# ALLPRINT-CAPBOARD-677512-ISO-PGM.net
KiCad netlist of a schematic drawn in Altium Designer
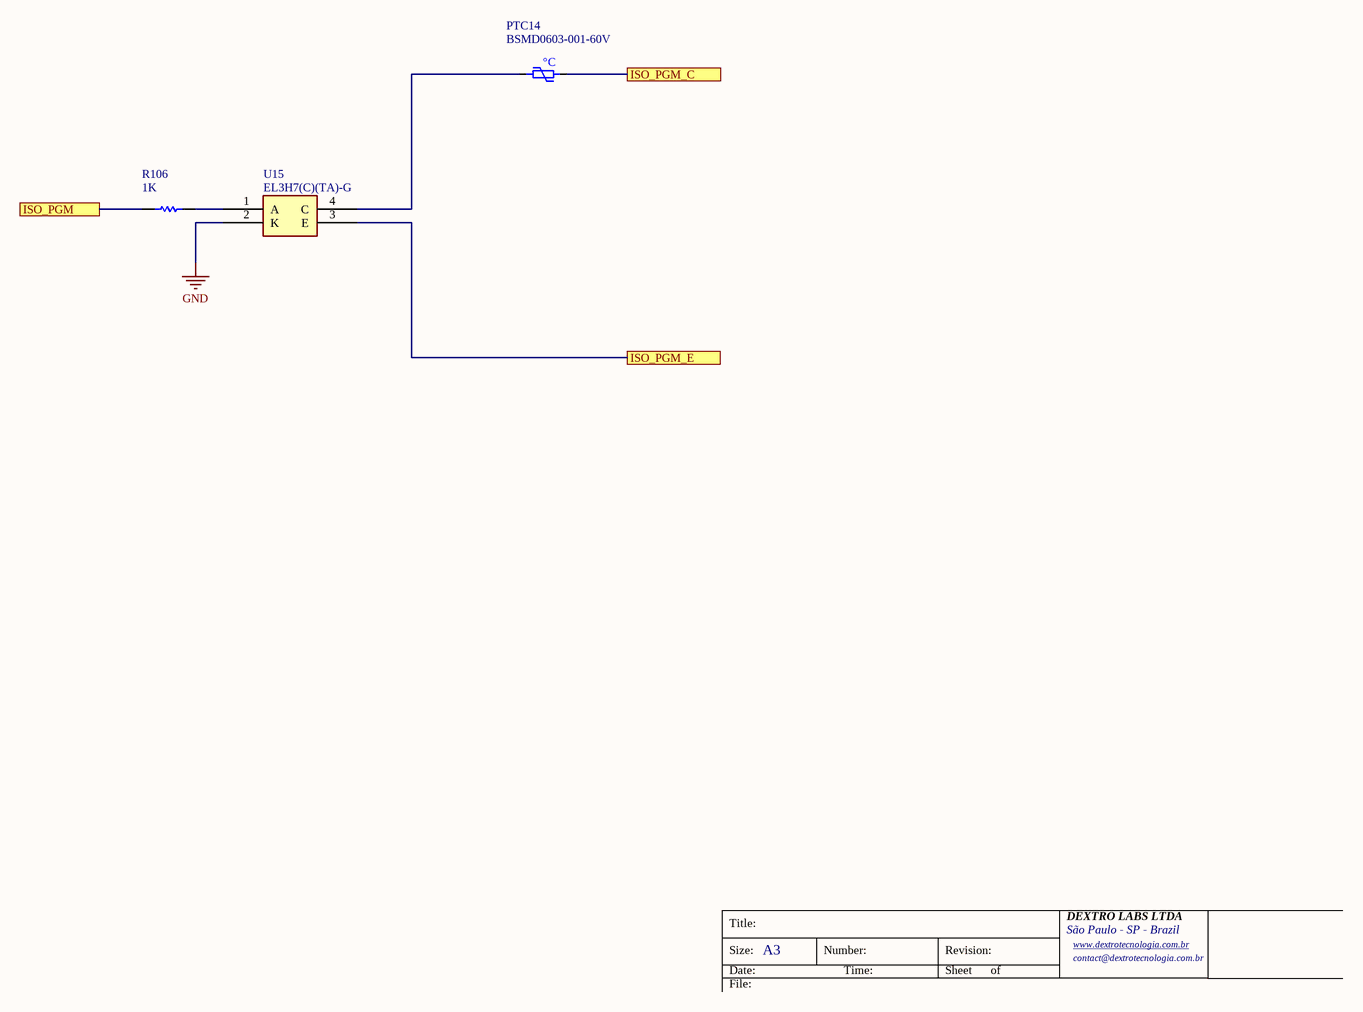
[diagram p0: ALLPRINT-CAPBOARD-677512-ISO-PGM.SchDoc]

(export (version "E")
  (design (tool "Eeschema 10.0.6"))
  (components
    (comp (ref "PTC14")
      (value "BSMD0603-001-60V")
      (footprint "PTC-0603")
      (description "60V 10mA 20A 50mA 15Ω 0603 PTC Resettable Fuses ROHS")
      (libsource (lib "dextro-labs") (part "PTC-FUSE-60V-10mA-0603"))
    )
    (comp (ref "R106")
      (value "1K")
      (footprint "RES-0603")
      (description "100mW Thick Film Resistor 75V ±100ppm/℃ ±1% 1kΩ 0603 Chip Resistor - Surface Mount ROHS")
      (libsource (lib "dextro-labs") (part "RES-1K-1%-100mW-0603"))
    )
    (comp (ref "U15")
      (value "EL3H7(C)(TA)-G")
      (footprint "SSOP-4")
      (libsource (lib "dextro-labs") (part "EL3H7(C)(TA)-G"))
    )
  )
  (nets
    (net (code "1") (name "/ISO_PGM") (class "Default")
      (node (ref "R106") (pin "1") (pinfunction "1_1") (pintype "passive"))
    )
    (net (code "2") (name "/ISO_PGM_C") (class "Default")
      (node (ref "PTC14") (pin "2") (pinfunction "2_2") (pintype "passive"))
    )
    (net (code "3") (name "/ISO_PGM_E") (class "Default")
      (node (ref "U15") (pin "3") (pinfunction "E_3") (pintype "passive"))
    )
    (net (code "4") (name "GND") (class "Default")
      (node (ref "U15") (pin "2") (pinfunction "K_2") (pintype "passive"))
    )
    (net (code "5") (name "Net-(U15-A)") (class "Default")
      (node (ref "R106") (pin "2") (pinfunction "2_2") (pintype "passive"))
      (node (ref "U15") (pin "1") (pinfunction "A_1") (pintype "passive"))
    )
    (net (code "6") (name "Net-(U15-C)") (class "Default")
      (node (ref "PTC14") (pin "1") (pinfunction "1_1") (pintype "passive"))
      (node (ref "U15") (pin "4") (pinfunction "C_4") (pintype "passive"))
    )
  )
)
